# FlashMemory.net
KiCad netlist of a schematic drawn in Altium Designer
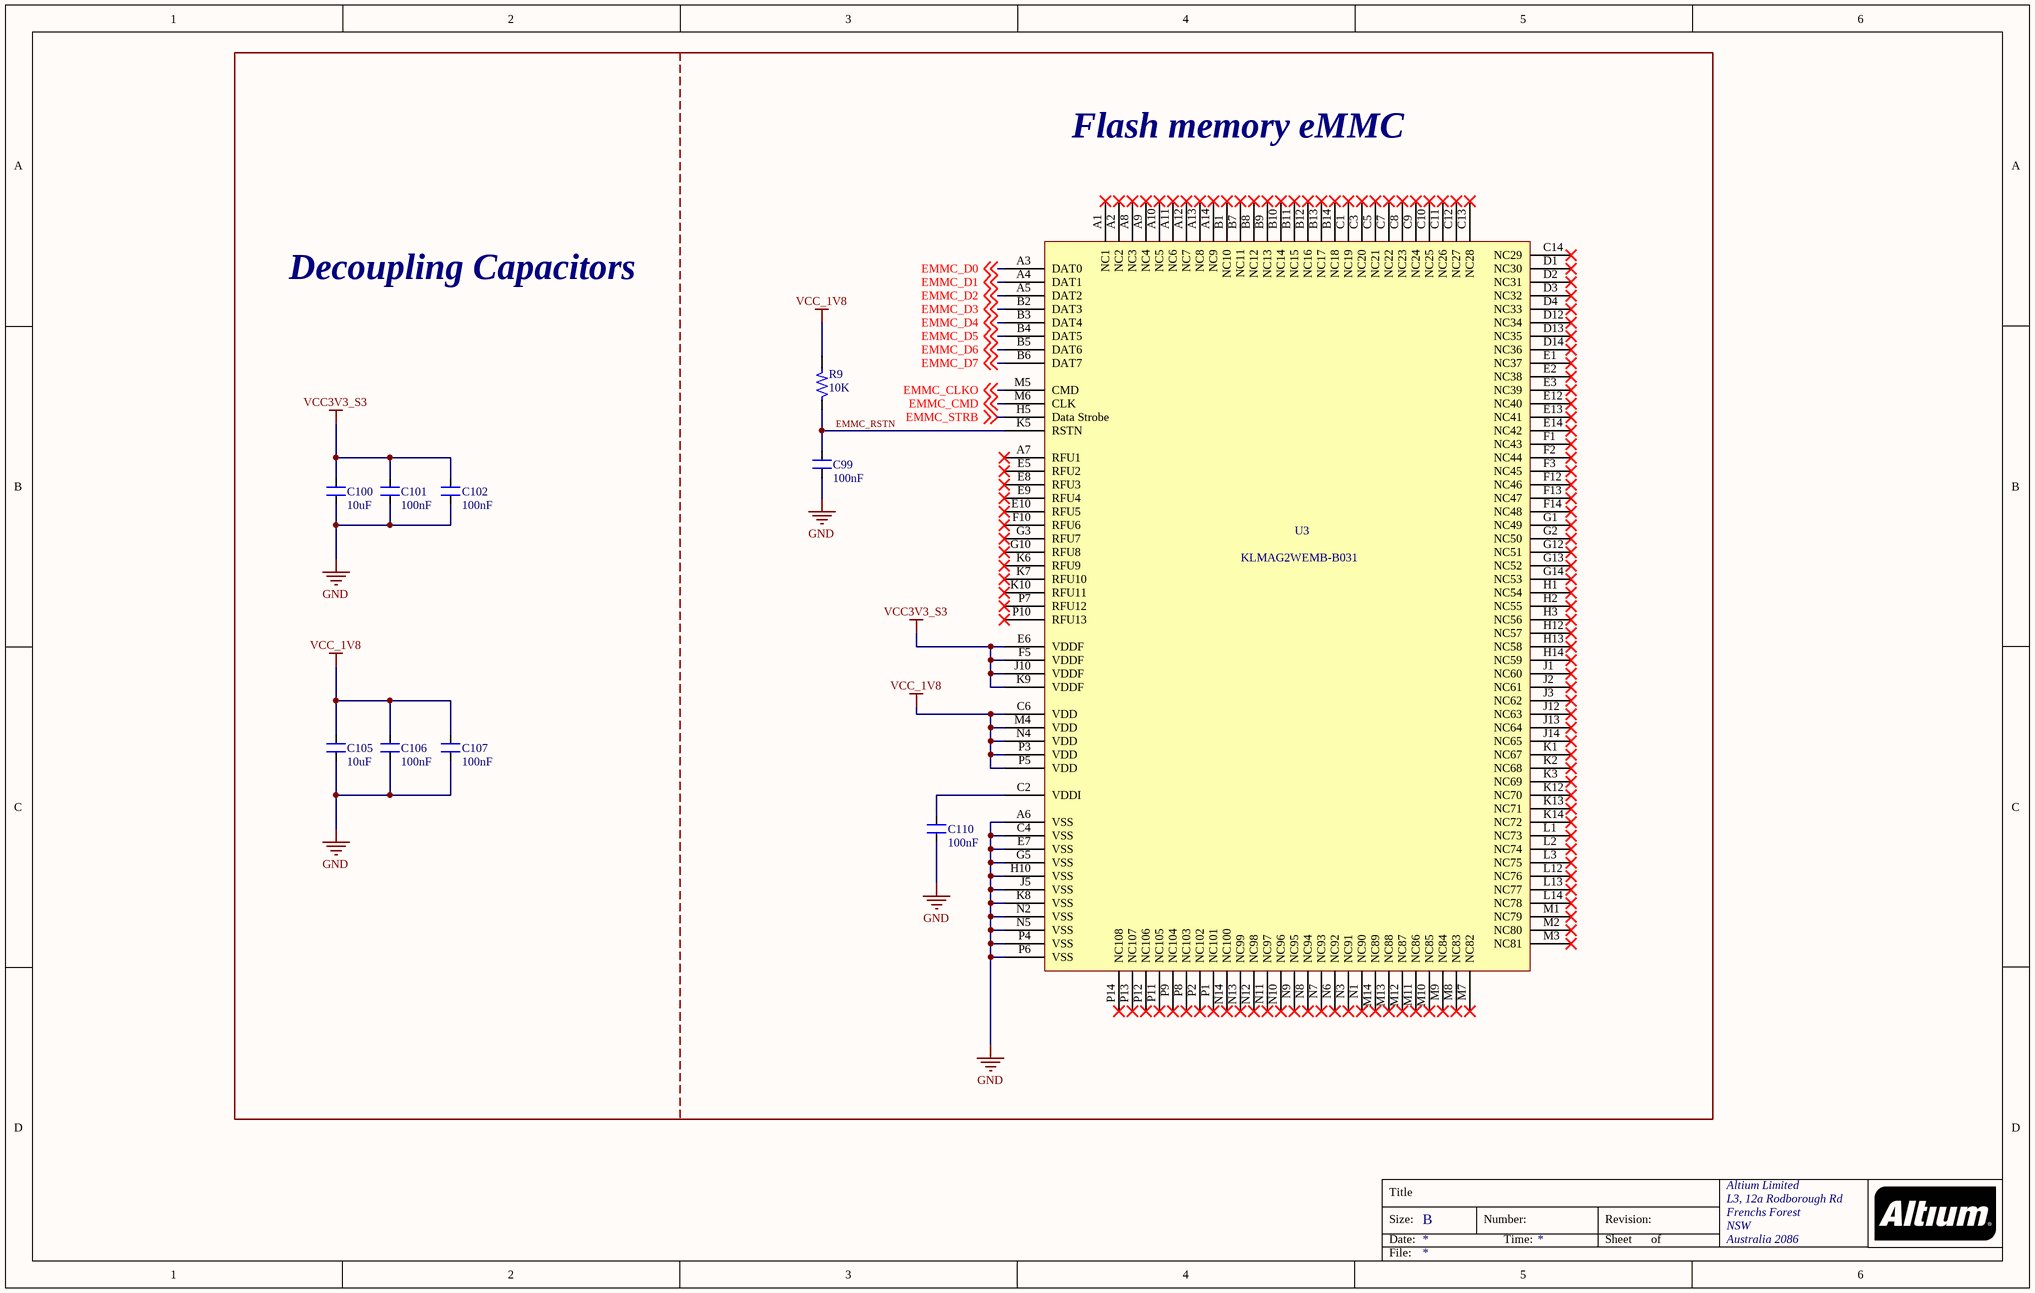
[diagram p0: FlashMemory.SchDoc]

(export (version "E")
  (design (tool "Eeschema 10.0.6"))
  (components
    (comp (ref "C99")
      (value "100nF")
      (footprint "CAP_0201")
      (description "0.1µF ±10% 25V Ceramic Capacitor X5R 0201 (0603 Metric)")
      (fields
        (field (name "MANUFACTURER") "TDK Corporation")
        (field (name "MANUFACTURER PART NUMBER") "C0603X5R1E104K030BB")
      )
      (libsource (lib "EsteemPCB_SOM_Course_intlib") (part "CAP_100nF-25V-10%-0201"))
    )
    (comp (ref "C100")
      (value "10uF")
      (footprint "CAP_0603")
      (description "10µF ±10% 25V Ceramic Capacitor X5R 0603 (1608 Metric)")
      (fields
        (field (name "MANUFACTURER") "Murata Electronics")
        (field (name "MANUFACTURER PART NUMBER") "GRM188R61E106KA73D")
      )
      (libsource (lib "EsteemPCB_SOM_Course_intlib") (part "CAP_10uF-25V-10%-0603"))
    )
    (comp (ref "C101")
      (value "100nF")
      (footprint "CAP_0201")
      (description "0.1µF ±10% 25V Ceramic Capacitor X5R 0201 (0603 Metric)")
      (fields
        (field (name "MANUFACTURER") "TDK Corporation")
        (field (name "MANUFACTURER PART NUMBER") "C0603X5R1E104K030BB")
      )
      (libsource (lib "EsteemPCB_SOM_Course_intlib") (part "CAP_100nF-25V-10%-0201"))
    )
    (comp (ref "C102")
      (value "100nF")
      (footprint "CAP_0201")
      (description "0.1µF ±10% 25V Ceramic Capacitor X5R 0201 (0603 Metric)")
      (fields
        (field (name "MANUFACTURER") "TDK Corporation")
        (field (name "MANUFACTURER PART NUMBER") "C0603X5R1E104K030BB")
      )
      (libsource (lib "EsteemPCB_SOM_Course_intlib") (part "CAP_100nF-25V-10%-0201"))
    )
    (comp (ref "C105")
      (value "10uF")
      (footprint "CAP_0603")
      (description "10µF ±10% 25V Ceramic Capacitor X5R 0603 (1608 Metric)")
      (fields
        (field (name "MANUFACTURER") "Murata Electronics")
        (field (name "MANUFACTURER PART NUMBER") "GRM188R61E106KA73D")
      )
      (libsource (lib "EsteemPCB_SOM_Course_intlib") (part "CAP_10uF-25V-10%-0603"))
    )
    (comp (ref "C106")
      (value "100nF")
      (footprint "CAP_0201")
      (description "0.1µF ±10% 25V Ceramic Capacitor X5R 0201 (0603 Metric)")
      (fields
        (field (name "MANUFACTURER") "TDK Corporation")
        (field (name "MANUFACTURER PART NUMBER") "C0603X5R1E104K030BB")
      )
      (libsource (lib "EsteemPCB_SOM_Course_intlib") (part "CAP_100nF-25V-10%-0201"))
    )
    (comp (ref "C107")
      (value "100nF")
      (footprint "CAP_0201")
      (description "0.1µF ±10% 25V Ceramic Capacitor X5R 0201 (0603 Metric)")
      (fields
        (field (name "MANUFACTURER") "TDK Corporation")
        (field (name "MANUFACTURER PART NUMBER") "C0603X5R1E104K030BB")
      )
      (libsource (lib "EsteemPCB_SOM_Course_intlib") (part "CAP_100nF-25V-10%-0201"))
    )
    (comp (ref "C110")
      (value "100nF")
      (footprint "CAP_0201")
      (description "0.1µF ±10% 25V Ceramic Capacitor X5R 0201 (0603 Metric)")
      (fields
        (field (name "MANUFACTURER") "TDK Corporation")
        (field (name "MANUFACTURER PART NUMBER") "C0603X5R1E104K030BB")
      )
      (libsource (lib "EsteemPCB_SOM_Course_intlib") (part "CAP_100nF-25V-10%-0201"))
    )
    (comp (ref "R9")
      (value "10K")
      (footprint "RES_0201")
      (description "10 kOhms ±1% 0.05W, 1/20W Chip Resistor 0201 (0603 Metric) Thick Film")
      (fields
        (field (name "MANUFACTURER") "Stackpole Electronics Inc")
        (field (name "MANUFACTURER PART NUMBER") "RMCF0201FT10K0")
      )
      (libsource (lib "EsteemPCB_SOM_Course_intlib") (part "RES_10K-0.05W-1%-0201"))
    )
    (comp (ref "U3")
      (value "KLMAG2WEMB-B031")
      (footprint "BGA153C50P14X14_1150X1300X70")
      (description "16GB NAND Flash Memory")
      (fields (field (name "MANUFACTURER") "Samsung Electronics"))
      (libsource (lib "EsteemPCB_SOM_Course_intlib") (part "IC_KLMAG2WEMB-B031"))
    )
  )
  (nets
    (net (code "1") (name "/EMMC_RSTN") (class "Default")
      (node (ref "C99") (pin "2") (pinfunction "2_2") (pintype "passive"))
      (node (ref "R9") (pin "1") (pinfunction "1_1") (pintype "passive"))
      (node (ref "U3") (pin "K5") (pinfunction "RSTN_K5") (pintype "passive"))
    )
    (net (code "2") (name "EMMC_CLKO") (class "Default")
      (node (ref "U3") (pin "M5") (pinfunction "CMD_M5") (pintype "passive"))
    )
    (net (code "3") (name "EMMC_CMD") (class "Default")
      (node (ref "U3") (pin "M6") (pinfunction "CLK_M6") (pintype "passive"))
    )
    (net (code "4") (name "EMMC_D0") (class "Default")
      (node (ref "U3") (pin "A3") (pinfunction "DAT0_A3") (pintype "passive"))
    )
    (net (code "5") (name "EMMC_D1") (class "Default")
      (node (ref "U3") (pin "A4") (pinfunction "DAT1_A4") (pintype "passive"))
    )
    (net (code "6") (name "EMMC_D2") (class "Default")
      (node (ref "U3") (pin "A5") (pinfunction "DAT2_A5") (pintype "passive"))
    )
    (net (code "7") (name "EMMC_D3") (class "Default")
      (node (ref "U3") (pin "B2") (pinfunction "DAT3_B2") (pintype "passive"))
    )
    (net (code "8") (name "EMMC_D4") (class "Default")
      (node (ref "U3") (pin "B3") (pinfunction "DAT4_B3") (pintype "passive"))
    )
    (net (code "9") (name "EMMC_D5") (class "Default")
      (node (ref "U3") (pin "B4") (pinfunction "DAT5_B4") (pintype "passive"))
    )
    (net (code "10") (name "EMMC_D6") (class "Default")
      (node (ref "U3") (pin "B5") (pinfunction "DAT6_B5") (pintype "passive"))
    )
    (net (code "11") (name "EMMC_D7") (class "Default")
      (node (ref "U3") (pin "B6") (pinfunction "DAT7_B6") (pintype "passive"))
    )
    (net (code "12") (name "EMMC_STRB") (class "Default")
      (node (ref "U3") (pin "H5") (pinfunction "Data_Strobe_H5") (pintype "passive"))
    )
    (net (code "13") (name "GND") (class "Default")
      (node (ref "C100") (pin "1") (pinfunction "1_1") (pintype "passive"))
      (node (ref "C101") (pin "1") (pinfunction "1_1") (pintype "passive"))
      (node (ref "C102") (pin "1") (pinfunction "1_1") (pintype "passive"))
      (node (ref "C105") (pin "1") (pinfunction "1_1") (pintype "passive"))
      (node (ref "C106") (pin "1") (pinfunction "1_1") (pintype "passive"))
      (node (ref "C107") (pin "1") (pinfunction "1_1") (pintype "passive"))
      (node (ref "C110") (pin "1") (pinfunction "1_1") (pintype "passive"))
      (node (ref "C99") (pin "1") (pinfunction "1_1") (pintype "passive"))
      (node (ref "U3") (pin "A6") (pinfunction "VSS_A6") (pintype "passive"))
      (node (ref "U3") (pin "C4") (pinfunction "VSS_C4") (pintype "passive"))
      (node (ref "U3") (pin "E7") (pinfunction "VSS_E7") (pintype "passive"))
      (node (ref "U3") (pin "G5") (pinfunction "VSS_G5") (pintype "passive"))
      (node (ref "U3") (pin "H10") (pinfunction "VSS_H10") (pintype "passive"))
      (node (ref "U3") (pin "J5") (pinfunction "VSS_J5") (pintype "passive"))
      (node (ref "U3") (pin "K8") (pinfunction "VSS_K8") (pintype "passive"))
      (node (ref "U3") (pin "N2") (pinfunction "VSS_N2") (pintype "passive"))
      (node (ref "U3") (pin "N5") (pinfunction "VSS_N5") (pintype "passive"))
      (node (ref "U3") (pin "P4") (pinfunction "VSS_P4") (pintype "passive"))
      (node (ref "U3") (pin "P6") (pinfunction "VSS_P6") (pintype "passive"))
    )
    (net (code "14") (name "Net-(U3-VDDI)") (class "Default")
      (node (ref "C110") (pin "2") (pinfunction "2_2") (pintype "passive"))
      (node (ref "U3") (pin "C2") (pinfunction "VDDI_C2") (pintype "passive"))
    )
    (net (code "15") (name "VCC3V3_S3") (class "Default")
      (node (ref "C100") (pin "2") (pinfunction "2_2") (pintype "passive"))
      (node (ref "C101") (pin "2") (pinfunction "2_2") (pintype "passive"))
      (node (ref "C102") (pin "2") (pinfunction "2_2") (pintype "passive"))
      (node (ref "U3") (pin "E6") (pinfunction "VDDF_E6") (pintype "passive"))
      (node (ref "U3") (pin "F5") (pinfunction "VDDF_F5") (pintype "passive"))
      (node (ref "U3") (pin "J10") (pinfunction "VDDF_J10") (pintype "passive"))
      (node (ref "U3") (pin "K9") (pinfunction "VDDF_K9") (pintype "passive"))
    )
    (net (code "16") (name "VCC_1V8") (class "Default")
      (node (ref "C105") (pin "2") (pinfunction "2_2") (pintype "passive"))
      (node (ref "C106") (pin "2") (pinfunction "2_2") (pintype "passive"))
      (node (ref "C107") (pin "2") (pinfunction "2_2") (pintype "passive"))
      (node (ref "R9") (pin "2") (pinfunction "2_2") (pintype "passive"))
      (node (ref "U3") (pin "C6") (pinfunction "VDD_C6") (pintype "passive"))
      (node (ref "U3") (pin "M4") (pinfunction "VDD_M4") (pintype "passive"))
      (node (ref "U3") (pin "N4") (pinfunction "VDD_N4") (pintype "passive"))
      (node (ref "U3") (pin "P3") (pinfunction "VDD_P3") (pintype "passive"))
      (node (ref "U3") (pin "P5") (pinfunction "VDD_P5") (pintype "passive"))
    )
    (net (code "17") (name "unconnected-(U3-NC1-PadA1)") (class "Default")
      (node (ref "U3") (pin "A1") (pinfunction "NC1_A1") (pintype "passive+no_connect"))
    )
    (net (code "18") (name "unconnected-(U3-NC2-PadA2)") (class "Default")
      (node (ref "U3") (pin "A2") (pinfunction "NC2_A2") (pintype "passive+no_connect"))
    )
    (net (code "19") (name "unconnected-(U3-NC3-PadA8)") (class "Default")
      (node (ref "U3") (pin "A8") (pinfunction "NC3_A8") (pintype "passive+no_connect"))
    )
    (net (code "20") (name "unconnected-(U3-NC4-PadA9)") (class "Default")
      (node (ref "U3") (pin "A9") (pinfunction "NC4_A9") (pintype "passive+no_connect"))
    )
    (net (code "21") (name "unconnected-(U3-NC5-PadA10)") (class "Default")
      (node (ref "U3") (pin "A10") (pinfunction "NC5_A10") (pintype "passive+no_connect"))
    )
    (net (code "22") (name "unconnected-(U3-NC6-PadA11)") (class "Default")
      (node (ref "U3") (pin "A11") (pinfunction "NC6_A11") (pintype "passive+no_connect"))
    )
    (net (code "23") (name "unconnected-(U3-NC7-PadA12)") (class "Default")
      (node (ref "U3") (pin "A12") (pinfunction "NC7_A12") (pintype "passive+no_connect"))
    )
    (net (code "24") (name "unconnected-(U3-NC8-PadA13)") (class "Default")
      (node (ref "U3") (pin "A13") (pinfunction "NC8_A13") (pintype "passive+no_connect"))
    )
    (net (code "25") (name "unconnected-(U3-NC9-PadA14)") (class "Default")
      (node (ref "U3") (pin "A14") (pinfunction "NC9_A14") (pintype "passive+no_connect"))
    )
    (net (code "26") (name "unconnected-(U3-NC10-PadB1)") (class "Default")
      (node (ref "U3") (pin "B1") (pinfunction "NC10_B1") (pintype "passive+no_connect"))
    )
    (net (code "27") (name "unconnected-(U3-NC11-PadB7)") (class "Default")
      (node (ref "U3") (pin "B7") (pinfunction "NC11_B7") (pintype "passive+no_connect"))
    )
    (net (code "28") (name "unconnected-(U3-NC12-PadB8)") (class "Default")
      (node (ref "U3") (pin "B8") (pinfunction "NC12_B8") (pintype "passive+no_connect"))
    )
    (net (code "29") (name "unconnected-(U3-NC13-PadB9)") (class "Default")
      (node (ref "U3") (pin "B9") (pinfunction "NC13_B9") (pintype "passive+no_connect"))
    )
    (net (code "30") (name "unconnected-(U3-NC14-PadB10)") (class "Default")
      (node (ref "U3") (pin "B10") (pinfunction "NC14_B10") (pintype "passive+no_connect"))
    )
    (net (code "31") (name "unconnected-(U3-NC15-PadB11)") (class "Default")
      (node (ref "U3") (pin "B11") (pinfunction "NC15_B11") (pintype "passive+no_connect"))
    )
    (net (code "32") (name "unconnected-(U3-NC16-PadB12)") (class "Default")
      (node (ref "U3") (pin "B12") (pinfunction "NC16_B12") (pintype "passive+no_connect"))
    )
    (net (code "33") (name "unconnected-(U3-NC17-PadB13)") (class "Default")
      (node (ref "U3") (pin "B13") (pinfunction "NC17_B13") (pintype "passive+no_connect"))
    )
    (net (code "34") (name "unconnected-(U3-NC18-PadB14)") (class "Default")
      (node (ref "U3") (pin "B14") (pinfunction "NC18_B14") (pintype "passive+no_connect"))
    )
    (net (code "35") (name "unconnected-(U3-NC19-PadC1)") (class "Default")
      (node (ref "U3") (pin "C1") (pinfunction "NC19_C1") (pintype "passive+no_connect"))
    )
    (net (code "36") (name "unconnected-(U3-NC20-PadC3)") (class "Default")
      (node (ref "U3") (pin "C3") (pinfunction "NC20_C3") (pintype "passive+no_connect"))
    )
    (net (code "37") (name "unconnected-(U3-NC21-PadC5)") (class "Default")
      (node (ref "U3") (pin "C5") (pinfunction "NC21_C5") (pintype "passive+no_connect"))
    )
    (net (code "38") (name "unconnected-(U3-NC22-PadC7)") (class "Default")
      (node (ref "U3") (pin "C7") (pinfunction "NC22_C7") (pintype "passive+no_connect"))
    )
    (net (code "39") (name "unconnected-(U3-NC23-PadC8)") (class "Default")
      (node (ref "U3") (pin "C8") (pinfunction "NC23_C8") (pintype "passive+no_connect"))
    )
    (net (code "40") (name "unconnected-(U3-NC24-PadC9)") (class "Default")
      (node (ref "U3") (pin "C9") (pinfunction "NC24_C9") (pintype "passive+no_connect"))
    )
    (net (code "41") (name "unconnected-(U3-NC25-PadC10)") (class "Default")
      (node (ref "U3") (pin "C10") (pinfunction "NC25_C10") (pintype "passive+no_connect"))
    )
    (net (code "42") (name "unconnected-(U3-NC26-PadC11)") (class "Default")
      (node (ref "U3") (pin "C11") (pinfunction "NC26_C11") (pintype "passive+no_connect"))
    )
    (net (code "43") (name "unconnected-(U3-NC27-PadC12)") (class "Default")
      (node (ref "U3") (pin "C12") (pinfunction "NC27_C12") (pintype "passive+no_connect"))
    )
    (net (code "44") (name "unconnected-(U3-NC28-PadC13)") (class "Default")
      (node (ref "U3") (pin "C13") (pinfunction "NC28_C13") (pintype "passive+no_connect"))
    )
    (net (code "45") (name "unconnected-(U3-NC29-PadC14)") (class "Default")
      (node (ref "U3") (pin "C14") (pinfunction "NC29_C14") (pintype "passive+no_connect"))
    )
    (net (code "46") (name "unconnected-(U3-NC30-PadD1)") (class "Default")
      (node (ref "U3") (pin "D1") (pinfunction "NC30_D1") (pintype "passive+no_connect"))
    )
    (net (code "47") (name "unconnected-(U3-NC31-PadD2)") (class "Default")
      (node (ref "U3") (pin "D2") (pinfunction "NC31_D2") (pintype "passive+no_connect"))
    )
    (net (code "48") (name "unconnected-(U3-NC32-PadD3)") (class "Default")
      (node (ref "U3") (pin "D3") (pinfunction "NC32_D3") (pintype "passive+no_connect"))
    )
    (net (code "49") (name "unconnected-(U3-NC33-PadD4)") (class "Default")
      (node (ref "U3") (pin "D4") (pinfunction "NC33_D4") (pintype "passive+no_connect"))
    )
    (net (code "50") (name "unconnected-(U3-NC34-PadD12)") (class "Default")
      (node (ref "U3") (pin "D12") (pinfunction "NC34_D12") (pintype "passive+no_connect"))
    )
    (net (code "51") (name "unconnected-(U3-NC35-PadD13)") (class "Default")
      (node (ref "U3") (pin "D13") (pinfunction "NC35_D13") (pintype "passive+no_connect"))
    )
    (net (code "52") (name "unconnected-(U3-NC36-PadD14)") (class "Default")
      (node (ref "U3") (pin "D14") (pinfunction "NC36_D14") (pintype "passive+no_connect"))
    )
    (net (code "53") (name "unconnected-(U3-NC37-PadE1)") (class "Default")
      (node (ref "U3") (pin "E1") (pinfunction "NC37_E1") (pintype "passive+no_connect"))
    )
    (net (code "54") (name "unconnected-(U3-NC38-PadE2)") (class "Default")
      (node (ref "U3") (pin "E2") (pinfunction "NC38_E2") (pintype "passive+no_connect"))
    )
    (net (code "55") (name "unconnected-(U3-NC39-PadE3)") (class "Default")
      (node (ref "U3") (pin "E3") (pinfunction "NC39_E3") (pintype "passive+no_connect"))
    )
    (net (code "56") (name "unconnected-(U3-NC40-PadE12)") (class "Default")
      (node (ref "U3") (pin "E12") (pinfunction "NC40_E12") (pintype "passive+no_connect"))
    )
    (net (code "57") (name "unconnected-(U3-NC41-PadE13)") (class "Default")
      (node (ref "U3") (pin "E13") (pinfunction "NC41_E13") (pintype "passive+no_connect"))
    )
    (net (code "58") (name "unconnected-(U3-NC42-PadE14)") (class "Default")
      (node (ref "U3") (pin "E14") (pinfunction "NC42_E14") (pintype "passive+no_connect"))
    )
    (net (code "59") (name "unconnected-(U3-NC43-PadF1)") (class "Default")
      (node (ref "U3") (pin "F1") (pinfunction "NC43_F1") (pintype "passive+no_connect"))
    )
    (net (code "60") (name "unconnected-(U3-NC44-PadF2)") (class "Default")
      (node (ref "U3") (pin "F2") (pinfunction "NC44_F2") (pintype "passive+no_connect"))
    )
    (net (code "61") (name "unconnected-(U3-NC45-PadF3)") (class "Default")
      (node (ref "U3") (pin "F3") (pinfunction "NC45_F3") (pintype "passive+no_connect"))
    )
    (net (code "62") (name "unconnected-(U3-NC46-PadF12)") (class "Default")
      (node (ref "U3") (pin "F12") (pinfunction "NC46_F12") (pintype "passive+no_connect"))
    )
    (net (code "63") (name "unconnected-(U3-NC47-PadF13)") (class "Default")
      (node (ref "U3") (pin "F13") (pinfunction "NC47_F13") (pintype "passive+no_connect"))
    )
    (net (code "64") (name "unconnected-(U3-NC48-PadF14)") (class "Default")
      (node (ref "U3") (pin "F14") (pinfunction "NC48_F14") (pintype "passive+no_connect"))
    )
    (net (code "65") (name "unconnected-(U3-NC49-PadG1)") (class "Default")
      (node (ref "U3") (pin "G1") (pinfunction "NC49_G1") (pintype "passive+no_connect"))
    )
    (net (code "66") (name "unconnected-(U3-NC50-PadG2)") (class "Default")
      (node (ref "U3") (pin "G2") (pinfunction "NC50_G2") (pintype "passive+no_connect"))
    )
    (net (code "67") (name "unconnected-(U3-NC51-PadG12)") (class "Default")
      (node (ref "U3") (pin "G12") (pinfunction "NC51_G12") (pintype "passive+no_connect"))
    )
    (net (code "68") (name "unconnected-(U3-NC52-PadG13)") (class "Default")
      (node (ref "U3") (pin "G13") (pinfunction "NC52_G13") (pintype "passive+no_connect"))
    )
    (net (code "69") (name "unconnected-(U3-NC53-PadG14)") (class "Default")
      (node (ref "U3") (pin "G14") (pinfunction "NC53_G14") (pintype "passive+no_connect"))
    )
    (net (code "70") (name "unconnected-(U3-NC54-PadH1)") (class "Default")
      (node (ref "U3") (pin "H1") (pinfunction "NC54_H1") (pintype "passive+no_connect"))
    )
    (net (code "71") (name "unconnected-(U3-NC55-PadH2)") (class "Default")
      (node (ref "U3") (pin "H2") (pinfunction "NC55_H2") (pintype "passive+no_connect"))
    )
    (net (code "72") (name "unconnected-(U3-NC56-PadH3)") (class "Default")
      (node (ref "U3") (pin "H3") (pinfunction "NC56_H3") (pintype "passive+no_connect"))
    )
    (net (code "73") (name "unconnected-(U3-NC57-PadH12)") (class "Default")
      (node (ref "U3") (pin "H12") (pinfunction "NC57_H12") (pintype "passive+no_connect"))
    )
    (net (code "74") (name "unconnected-(U3-NC58-PadH13)") (class "Default")
      (node (ref "U3") (pin "H13") (pinfunction "NC58_H13") (pintype "passive+no_connect"))
    )
    (net (code "75") (name "unconnected-(U3-NC59-PadH14)") (class "Default")
      (node (ref "U3") (pin "H14") (pinfunction "NC59_H14") (pintype "passive+no_connect"))
    )
    (net (code "76") (name "unconnected-(U3-NC60-PadJ1)") (class "Default")
      (node (ref "U3") (pin "J1") (pinfunction "NC60_J1") (pintype "passive+no_connect"))
    )
    (net (code "77") (name "unconnected-(U3-NC61-PadJ2)") (class "Default")
      (node (ref "U3") (pin "J2") (pinfunction "NC61_J2") (pintype "passive+no_connect"))
    )
    (net (code "78") (name "unconnected-(U3-NC62-PadJ3)") (class "Default")
      (node (ref "U3") (pin "J3") (pinfunction "NC62_J3") (pintype "passive+no_connect"))
    )
    (net (code "79") (name "unconnected-(U3-NC63-PadJ12)") (class "Default")
      (node (ref "U3") (pin "J12") (pinfunction "NC63_J12") (pintype "passive+no_connect"))
    )
    (net (code "80") (name "unconnected-(U3-NC64-PadJ13)") (class "Default")
      (node (ref "U3") (pin "J13") (pinfunction "NC64_J13") (pintype "passive+no_connect"))
    )
    (net (code "81") (name "unconnected-(U3-NC65-PadJ14)") (class "Default")
      (node (ref "U3") (pin "J14") (pinfunction "NC65_J14") (pintype "passive+no_connect"))
    )
    (net (code "82") (name "unconnected-(U3-NC67-PadK1)") (class "Default")
      (node (ref "U3") (pin "K1") (pinfunction "NC67_K1") (pintype "passive+no_connect"))
    )
    (net (code "83") (name "unconnected-(U3-NC68-PadK2)") (class "Default")
      (node (ref "U3") (pin "K2") (pinfunction "NC68_K2") (pintype "passive+no_connect"))
    )
    (net (code "84") (name "unconnected-(U3-NC69-PadK3)") (class "Default")
      (node (ref "U3") (pin "K3") (pinfunction "NC69_K3") (pintype "passive+no_connect"))
    )
    (net (code "85") (name "unconnected-(U3-NC70-PadK12)") (class "Default")
      (node (ref "U3") (pin "K12") (pinfunction "NC70_K12") (pintype "passive+no_connect"))
    )
    (net (code "86") (name "unconnected-(U3-NC71-PadK13)") (class "Default")
      (node (ref "U3") (pin "K13") (pinfunction "NC71_K13") (pintype "passive+no_connect"))
    )
    (net (code "87") (name "unconnected-(U3-NC72-PadK14)") (class "Default")
      (node (ref "U3") (pin "K14") (pinfunction "NC72_K14") (pintype "passive+no_connect"))
    )
    (net (code "88") (name "unconnected-(U3-NC73-PadL1)") (class "Default")
      (node (ref "U3") (pin "L1") (pinfunction "NC73_L1") (pintype "passive+no_connect"))
    )
    (net (code "89") (name "unconnected-(U3-NC74-PadL2)") (class "Default")
      (node (ref "U3") (pin "L2") (pinfunction "NC74_L2") (pintype "passive+no_connect"))
    )
    (net (code "90") (name "unconnected-(U3-NC75-PadL3)") (class "Default")
      (node (ref "U3") (pin "L3") (pinfunction "NC75_L3") (pintype "passive+no_connect"))
    )
    (net (code "91") (name "unconnected-(U3-NC76-PadL12)") (class "Default")
      (node (ref "U3") (pin "L12") (pinfunction "NC76_L12") (pintype "passive+no_connect"))
    )
    (net (code "92") (name "unconnected-(U3-NC77-PadL13)") (class "Default")
      (node (ref "U3") (pin "L13") (pinfunction "NC77_L13") (pintype "passive+no_connect"))
    )
    (net (code "93") (name "unconnected-(U3-NC78-PadL14)") (class "Default")
      (node (ref "U3") (pin "L14") (pinfunction "NC78_L14") (pintype "passive+no_connect"))
    )
    (net (code "94") (name "unconnected-(U3-NC79-PadM1)") (class "Default")
      (node (ref "U3") (pin "M1") (pinfunction "NC79_M1") (pintype "passive+no_connect"))
    )
    (net (code "95") (name "unconnected-(U3-NC80-PadM2)") (class "Default")
      (node (ref "U3") (pin "M2") (pinfunction "NC80_M2") (pintype "passive+no_connect"))
    )
    (net (code "96") (name "unconnected-(U3-NC81-PadM3)") (class "Default")
      (node (ref "U3") (pin "M3") (pinfunction "NC81_M3") (pintype "passive+no_connect"))
    )
    (net (code "97") (name "unconnected-(U3-NC82-PadM7)") (class "Default")
      (node (ref "U3") (pin "M7") (pinfunction "NC82_M7") (pintype "passive+no_connect"))
    )
    (net (code "98") (name "unconnected-(U3-NC83-PadM8)") (class "Default")
      (node (ref "U3") (pin "M8") (pinfunction "NC83_M8") (pintype "passive+no_connect"))
    )
    (net (code "99") (name "unconnected-(U3-NC84-PadM9)") (class "Default")
      (node (ref "U3") (pin "M9") (pinfunction "NC84_M9") (pintype "passive+no_connect"))
    )
    (net (code "100") (name "unconnected-(U3-NC85-PadM10)") (class "Default")
      (node (ref "U3") (pin "M10") (pinfunction "NC85_M10") (pintype "passive+no_connect"))
    )
    (net (code "101") (name "unconnected-(U3-NC86-PadM11)") (class "Default")
      (node (ref "U3") (pin "M11") (pinfunction "NC86_M11") (pintype "passive+no_connect"))
    )
    (net (code "102") (name "unconnected-(U3-NC87-PadM12)") (class "Default")
      (node (ref "U3") (pin "M12") (pinfunction "NC87_M12") (pintype "passive+no_connect"))
    )
    (net (code "103") (name "unconnected-(U3-NC88-PadM13)") (class "Default")
      (node (ref "U3") (pin "M13") (pinfunction "NC88_M13") (pintype "passive+no_connect"))
    )
    (net (code "104") (name "unconnected-(U3-NC89-PadM14)") (class "Default")
      (node (ref "U3") (pin "M14") (pinfunction "NC89_M14") (pintype "passive+no_connect"))
    )
    (net (code "105") (name "unconnected-(U3-NC90-PadN1)") (class "Default")
      (node (ref "U3") (pin "N1") (pinfunction "NC90_N1") (pintype "passive+no_connect"))
    )
    (net (code "106") (name "unconnected-(U3-NC91-PadN3)") (class "Default")
      (node (ref "U3") (pin "N3") (pinfunction "NC91_N3") (pintype "passive+no_connect"))
    )
    (net (code "107") (name "unconnected-(U3-NC92-PadN6)") (class "Default")
      (node (ref "U3") (pin "N6") (pinfunction "NC92_N6") (pintype "passive+no_connect"))
    )
    (net (code "108") (name "unconnected-(U3-NC93-PadN7)") (class "Default")
      (node (ref "U3") (pin "N7") (pinfunction "NC93_N7") (pintype "passive+no_connect"))
    )
    (net (code "109") (name "unconnected-(U3-NC94-PadN8)") (class "Default")
      (node (ref "U3") (pin "N8") (pinfunction "NC94_N8") (pintype "passive+no_connect"))
    )
    (net (code "110") (name "unconnected-(U3-NC95-PadN9)") (class "Default")
      (node (ref "U3") (pin "N9") (pinfunction "NC95_N9") (pintype "passive+no_connect"))
    )
    (net (code "111") (name "unconnected-(U3-NC96-PadN10)") (class "Default")
      (node (ref "U3") (pin "N10") (pinfunction "NC96_N10") (pintype "passive+no_connect"))
    )
    (net (code "112") (name "unconnected-(U3-NC97-PadN11)") (class "Default")
      (node (ref "U3") (pin "N11") (pinfunction "NC97_N11") (pintype "passive+no_connect"))
    )
    (net (code "113") (name "unconnected-(U3-NC98-PadN12)") (class "Default")
      (node (ref "U3") (pin "N12") (pinfunction "NC98_N12") (pintype "passive+no_connect"))
    )
    (net (code "114") (name "unconnected-(U3-NC99-PadN13)") (class "Default")
      (node (ref "U3") (pin "N13") (pinfunction "NC99_N13") (pintype "passive+no_connect"))
    )
    (net (code "115") (name "unconnected-(U3-NC100-PadN14)") (class "Default")
      (node (ref "U3") (pin "N14") (pinfunction "NC100_N14") (pintype "passive+no_connect"))
    )
    (net (code "116") (name "unconnected-(U3-NC101-PadP1)") (class "Default")
      (node (ref "U3") (pin "P1") (pinfunction "NC101_P1") (pintype "passive+no_connect"))
    )
    (net (code "117") (name "unconnected-(U3-NC102-PadP2)") (class "Default")
      (node (ref "U3") (pin "P2") (pinfunction "NC102_P2") (pintype "passive+no_connect"))
    )
    (net (code "118") (name "unconnected-(U3-NC103-PadP8)") (class "Default")
      (node (ref "U3") (pin "P8") (pinfunction "NC103_P8") (pintype "passive+no_connect"))
    )
    (net (code "119") (name "unconnected-(U3-NC104-PadP9)") (class "Default")
      (node (ref "U3") (pin "P9") (pinfunction "NC104_P9") (pintype "passive+no_connect"))
    )
    (net (code "120") (name "unconnected-(U3-NC105-PadP11)") (class "Default")
      (node (ref "U3") (pin "P11") (pinfunction "NC105_P11") (pintype "passive+no_connect"))
    )
    (net (code "121") (name "unconnected-(U3-NC106-PadP12)") (class "Default")
      (node (ref "U3") (pin "P12") (pinfunction "NC106_P12") (pintype "passive+no_connect"))
    )
    (net (code "122") (name "unconnected-(U3-NC107-PadP13)") (class "Default")
      (node (ref "U3") (pin "P13") (pinfunction "NC107_P13") (pintype "passive+no_connect"))
    )
    (net (code "123") (name "unconnected-(U3-NC108-PadP14)") (class "Default")
      (node (ref "U3") (pin "P14") (pinfunction "NC108_P14") (pintype "passive+no_connect"))
    )
    (net (code "124") (name "unconnected-(U3-RFU1-PadA7)") (class "Default")
      (node (ref "U3") (pin "A7") (pinfunction "RFU1_A7") (pintype "passive+no_connect"))
    )
    (net (code "125") (name "unconnected-(U3-RFU2-PadE5)") (class "Default")
      (node (ref "U3") (pin "E5") (pinfunction "RFU2_E5") (pintype "passive+no_connect"))
    )
    (net (code "126") (name "unconnected-(U3-RFU3-PadE8)") (class "Default")
      (node (ref "U3") (pin "E8") (pinfunction "RFU3_E8") (pintype "passive+no_connect"))
    )
    (net (code "127") (name "unconnected-(U3-RFU4-PadE9)") (class "Default")
      (node (ref "U3") (pin "E9") (pinfunction "RFU4_E9") (pintype "passive+no_connect"))
    )
    (net (code "128") (name "unconnected-(U3-RFU5-PadE10)") (class "Default")
      (node (ref "U3") (pin "E10") (pinfunction "RFU5_E10") (pintype "passive+no_connect"))
    )
    (net (code "129") (name "unconnected-(U3-RFU6-PadF10)") (class "Default")
      (node (ref "U3") (pin "F10") (pinfunction "RFU6_F10") (pintype "passive+no_connect"))
    )
    (net (code "130") (name "unconnected-(U3-RFU7-PadG3)") (class "Default")
      (node (ref "U3") (pin "G3") (pinfunction "RFU7_G3") (pintype "passive+no_connect"))
    )
    (net (code "131") (name "unconnected-(U3-RFU8-PadG10)") (class "Default")
      (node (ref "U3") (pin "G10") (pinfunction "RFU8_G10") (pintype "passive+no_connect"))
    )
    (net (code "132") (name "unconnected-(U3-RFU9-PadK6)") (class "Default")
      (node (ref "U3") (pin "K6") (pinfunction "RFU9_K6") (pintype "passive+no_connect"))
    )
    (net (code "133") (name "unconnected-(U3-RFU10-PadK7)") (class "Default")
      (node (ref "U3") (pin "K7") (pinfunction "RFU10_K7") (pintype "passive+no_connect"))
    )
    (net (code "134") (name "unconnected-(U3-RFU11-PadK10)") (class "Default")
      (node (ref "U3") (pin "K10") (pinfunction "RFU11_K10") (pintype "passive+no_connect"))
    )
    (net (code "135") (name "unconnected-(U3-RFU12-PadP7)") (class "Default")
      (node (ref "U3") (pin "P7") (pinfunction "RFU12_P7") (pintype "passive+no_connect"))
    )
    (net (code "136") (name "unconnected-(U3-RFU13-PadP10)") (class "Default")
      (node (ref "U3") (pin "P10") (pinfunction "RFU13_P10") (pintype "passive+no_connect"))
    )
  )
)
